# PCB1.net
KiCad netlist of a schematic drawn in Altium Designer
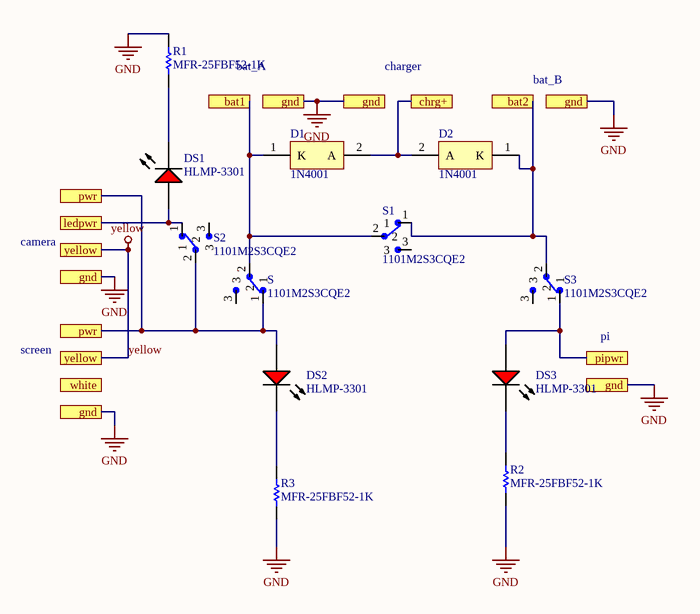
[diagram p0: PCB1.SchDoc]

(export (version "E")
  (design (tool "Eeschema 10.0.6"))
  (components
    (comp (ref "D1")
      (value "1N4001")
      (footprint "ONSC-AXIAL_LEAD-2-59-10_P")
      (description "Standard Recovery Rectifier, 2-Pin Axial_Lead, Pb-Free, Bulk Bag")
      (fields (field (name "MANUFACTURER") "On Semiconductor"))
      (libsource (lib "Altium Content Vault") (part "ONSC-D-K1A2-2_A"))
    )
    (comp (ref "D2")
      (value "1N4001")
      (footprint "ONSC-AXIAL_LEAD-2-59-10_P")
      (description "Standard Recovery Rectifier, 2-Pin Axial_Lead, Pb-Free, Bulk Bag")
      (fields (field (name "MANUFACTURER") "On Semiconductor"))
      (libsource (lib "") (part "ONSC-D-K1A2-2_A_1"))
    )
    (comp (ref "DS1")
      (value "HLMP-3301")
      (footprint "AVAG-HLMP-3301-2")
      (description "T-1 3/4 (5 mm) Diffused LED Lamp, 1.9 V, -40 to 100 degC, 2-Pin THD, RoHS, Bulk")
      (fields (field (name "MANUFACTURER") "Avago"))
      (libsource (lib "Altium Content Vault") (part "LED-RED-K1A2-2"))
    )
    (comp (ref "DS2")
      (value "HLMP-3301")
      (footprint "AVAG-HLMP-3301-2")
      (description "T-1 3/4 (5 mm) Diffused LED Lamp, 1.9 V, -40 to 100 degC, 2-Pin THD, RoHS, Bulk")
      (fields (field (name "MANUFACTURER") "Avago"))
      (libsource (lib "Altium Content Vault") (part "LED-RED-K1A2-2"))
    )
    (comp (ref "DS3")
      (value "HLMP-3301")
      (footprint "AVAG-HLMP-3301-2")
      (description "T-1 3/4 (5 mm) Diffused LED Lamp, 1.9 V, -40 to 100 degC, 2-Pin THD, RoHS, Bulk")
      (fields (field (name "MANUFACTURER") "Avago"))
      (libsource (lib "Altium Content Vault") (part "LED-RED-K1A2-2"))
    )
    (comp (ref "R1")
      (value "MFR-25FBF52-1K")
      (footprint "RESA60-630X240")
      (description "Axial Resistor, 1 KOhm, +/- 1%, 250 mW, -55 to 155 degC, 2-Pin THD, RoHS, Bulk")
      (fields (field (name "TOLERANCE") "1%"))
      (libsource (lib "Altium Content Vault") (part "RES-2"))
    )
    (comp (ref "R2")
      (value "MFR-25FBF52-1K")
      (footprint "RESA60-630X240")
      (description "Axial Resistor, 1 KOhm, +/- 1%, 250 mW, -55 to 155 degC, 2-Pin THD, RoHS, Bulk")
      (fields (field (name "TOLERANCE") "1%"))
      (libsource (lib "Altium Content Vault") (part "RES-2"))
    )
    (comp (ref "R3")
      (value "MFR-25FBF52-1K")
      (footprint "RESA60-630X240")
      (description "Axial Resistor, 1 KOhm, +/- 1%, 250 mW, -55 to 155 degC, 2-Pin THD, RoHS, Bulk")
      (fields (field (name "TOLERANCE") "1%"))
      (libsource (lib "Altium Content Vault") (part "RES-2"))
    )
    (comp (ref "S")
      (value "1101M2S3CQE2")
      (footprint "SW_1101M2S3CQE2")
      (description "Slide Switch SPDT Through Hole")
      (fields (field (name "DIGI-KEY_PART_NUMBER") "CKN5001-ND") (field (name "MF") "C&K"))
      (libsource (lib "1101M2S3CQE2") (part "1101M2S3CQE2"))
    )
    (comp (ref "S1")
      (value "1101M2S3CQE2")
      (footprint "SW_1101M2S3CQE2")
      (description "Slide Switch SPDT Through Hole")
      (fields (field (name "DIGI-KEY_PART_NUMBER") "CKN5001-ND") (field (name "MF") "C&K"))
      (libsource (lib "1101M2S3CQE2") (part "1101M2S3CQE2"))
    )
    (comp (ref "S2")
      (value "1101M2S3CQE2")
      (footprint "SW_1101M2S3CQE2")
      (description "Slide Switch SPDT Through Hole")
      (fields (field (name "DIGI-KEY_PART_NUMBER") "CKN5001-ND") (field (name "MF") "C&K"))
      (libsource (lib "1101M2S3CQE2") (part "1101M2S3CQE2"))
    )
    (comp (ref "S3")
      (value "1101M2S3CQE2")
      (footprint "SW_1101M2S3CQE2")
      (description "Slide Switch SPDT Through Hole")
      (fields (field (name "DIGI-KEY_PART_NUMBER") "CKN5001-ND") (field (name "MF") "C&K"))
      (libsource (lib "1101M2S3CQE2") (part "1101M2S3CQE2"))
    )
  )
  (nets
    (net (code "1") (name "/bat1") (class "Default")
      (node (ref "D1") (pin "1") (pinfunction "K_1") (pintype "passive"))
      (node (ref "S") (pin "2") (pinfunction "2_2") (pintype "passive"))
      (node (ref "S1") (pin "2") (pinfunction "2_2") (pintype "passive"))
    )
    (net (code "2") (name "/bat2") (class "Default")
      (node (ref "D2") (pin "1") (pinfunction "K_1") (pintype "passive"))
      (node (ref "S1") (pin "1") (pinfunction "1_1") (pintype "passive"))
      (node (ref "S3") (pin "2") (pinfunction "2_2") (pintype "passive"))
    )
    (net (code "3") (name "/chrg+") (class "Default")
      (node (ref "D1") (pin "2") (pinfunction "A_2") (pintype "passive"))
      (node (ref "D2") (pin "2") (pinfunction "A_2") (pintype "passive"))
    )
    (net (code "4") (name "/ledpwr") (class "Default")
      (node (ref "DS1") (pin "2") (pinfunction "A_2") (pintype "passive"))
      (node (ref "S2") (pin "1") (pinfunction "1_1") (pintype "passive"))
    )
    (net (code "5") (name "/pipwr") (class "Default")
      (node (ref "DS3") (pin "2") (pinfunction "A_2") (pintype "passive"))
      (node (ref "S3") (pin "1") (pinfunction "1_1") (pintype "passive"))
    )
    (net (code "6") (name "/pwr") (class "Default")
      (node (ref "DS2") (pin "2") (pinfunction "A_2") (pintype "passive"))
      (node (ref "S") (pin "1") (pinfunction "1_1") (pintype "passive"))
      (node (ref "S2") (pin "2") (pinfunction "2_2") (pintype "passive"))
    )
    (net (code "8") (name "GND") (class "Default")
      (node (ref "R1") (pin "2") (pinfunction "2_2") (pintype "passive"))
      (node (ref "R2") (pin "1") (pinfunction "1_1") (pintype "passive"))
      (node (ref "R3") (pin "1") (pinfunction "1_1") (pintype "passive"))
    )
    (net (code "9") (name "Net-(DS1-K)") (class "Default")
      (node (ref "DS1") (pin "1") (pinfunction "K_1") (pintype "passive"))
      (node (ref "R1") (pin "1") (pinfunction "1_1") (pintype "passive"))
    )
    (net (code "10") (name "Net-(DS2-K)") (class "Default")
      (node (ref "DS2") (pin "1") (pinfunction "K_1") (pintype "passive"))
      (node (ref "R3") (pin "2") (pinfunction "2_2") (pintype "passive"))
    )
    (net (code "11") (name "Net-(DS3-K)") (class "Default")
      (node (ref "DS3") (pin "1") (pinfunction "K_1") (pintype "passive"))
      (node (ref "R2") (pin "2") (pinfunction "2_2") (pintype "passive"))
    )
    (net (code "12") (name "unconnected-(S-Pad3)") (class "Default")
      (node (ref "S") (pin "3") (pinfunction "3_3") (pintype "passive"))
    )
    (net (code "13") (name "unconnected-(S1-Pad3)") (class "Default")
      (node (ref "S1") (pin "3") (pinfunction "3_3") (pintype "passive"))
    )
    (net (code "14") (name "unconnected-(S2-Pad3)") (class "Default")
      (node (ref "S2") (pin "3") (pinfunction "3_3") (pintype "passive"))
    )
    (net (code "15") (name "unconnected-(S3-Pad3)") (class "Default")
      (node (ref "S3") (pin "3") (pinfunction "3_3") (pintype "passive"))
    )
  )
)
